# ProPrj_ESP-ARGB_2026-06-01.net
KiCad netlist of a schematic drawn in EasyEDA Pro
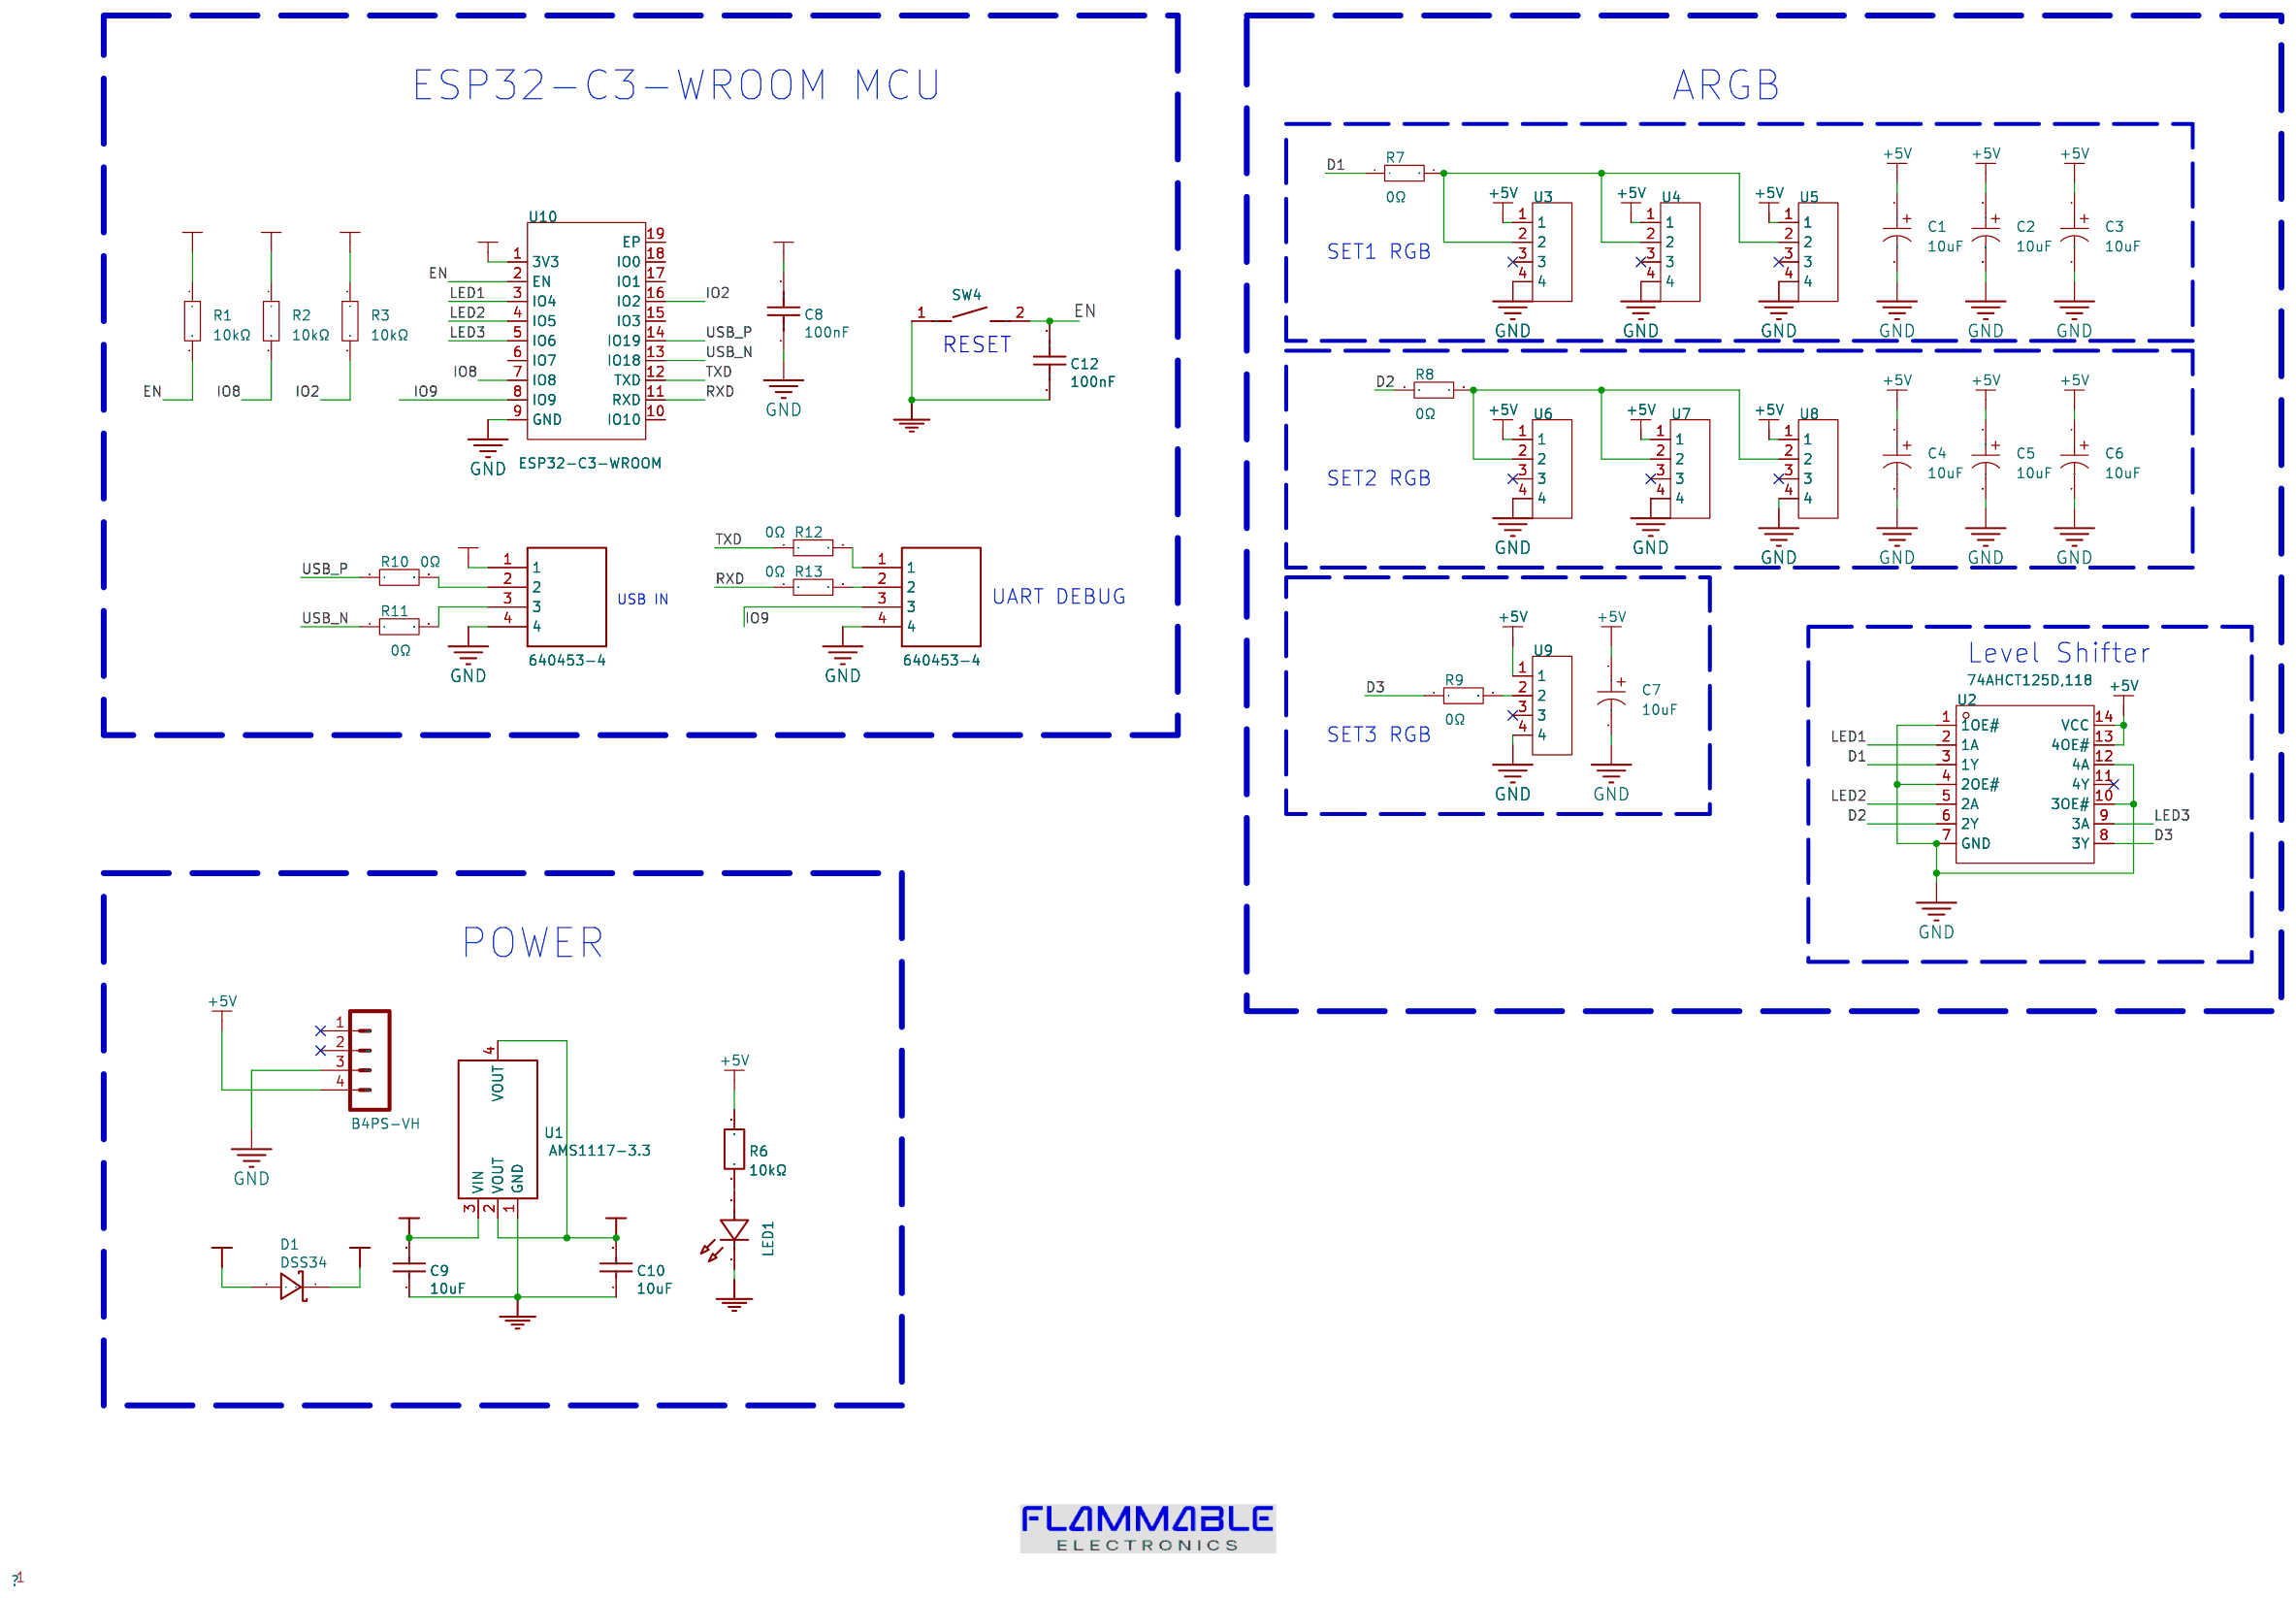
[diagram p0: schematic sheet]

(export (version "E")
  (design (tool "Eeschema 10.0.6"))
  (components
    (comp (ref "C1")
      (value "10uF")
      (footprint "easyedapro:CAP-SMD_BD4.0-L4.3-W4.3-LS5.0-FD")
      (fields
        (field (name "Manufacturer Part") "RVT1E100M0405 10UF 25V")
        (field (name "Manufacturer") "DMBJ(振宝佳)")
      )
      (libsource (lib "easyedapro") (part "RVT1E100M0405 10UF 25V"))
    )
    (comp (ref "C2")
      (value "10uF")
      (footprint "easyedapro:CAP-SMD_BD4.0-L4.3-W4.3-LS5.0-FD")
      (fields
        (field (name "Manufacturer Part") "RVT1E100M0405 10UF 25V")
        (field (name "Manufacturer") "DMBJ(振宝佳)")
      )
      (libsource (lib "easyedapro") (part "RVT1E100M0405 10UF 25V"))
    )
    (comp (ref "C3")
      (value "10uF")
      (footprint "easyedapro:CAP-SMD_BD4.0-L4.3-W4.3-LS5.0-FD")
      (fields
        (field (name "Manufacturer Part") "RVT1E100M0405 10UF 25V")
        (field (name "Manufacturer") "DMBJ(振宝佳)")
      )
      (libsource (lib "easyedapro") (part "RVT1E100M0405 10UF 25V"))
    )
    (comp (ref "C4")
      (value "10uF")
      (footprint "easyedapro:CAP-SMD_BD4.0-L4.3-W4.3-LS5.0-FD")
      (fields
        (field (name "Manufacturer Part") "RVT1E100M0405 10UF 25V")
        (field (name "Manufacturer") "DMBJ(振宝佳)")
      )
      (libsource (lib "easyedapro") (part "RVT1E100M0405 10UF 25V"))
    )
    (comp (ref "C5")
      (value "10uF")
      (footprint "easyedapro:CAP-SMD_BD4.0-L4.3-W4.3-LS5.0-FD")
      (fields
        (field (name "Manufacturer Part") "RVT1E100M0405 10UF 25V")
        (field (name "Manufacturer") "DMBJ(振宝佳)")
      )
      (libsource (lib "easyedapro") (part "RVT1E100M0405 10UF 25V"))
    )
    (comp (ref "C6")
      (value "10uF")
      (footprint "easyedapro:CAP-SMD_BD4.0-L4.3-W4.3-LS5.0-FD")
      (fields
        (field (name "Manufacturer Part") "RVT1E100M0405 10UF 25V")
        (field (name "Manufacturer") "DMBJ(振宝佳)")
      )
      (libsource (lib "easyedapro") (part "RVT1E100M0405 10UF 25V"))
    )
    (comp (ref "C7")
      (value "10uF")
      (footprint "easyedapro:CAP-SMD_BD4.0-L4.3-W4.3-LS5.0-FD")
      (fields
        (field (name "Manufacturer Part") "RVT1E100M0405 10UF 25V")
        (field (name "Manufacturer") "DMBJ(振宝佳)")
      )
      (libsource (lib "easyedapro") (part "RVT1E100M0405 10UF 25V"))
    )
    (comp (ref "C8")
      (value "100nF")
      (footprint "easyedapro:C0805")
      (fields (field (name "Manufacturer Part") "C2012X7R1H104KT0J0N") (field (name "Manufacturer") "TDK"))
      (libsource (lib "easyedapro") (part "100nF"))
    )
    (comp (ref "C9")
      (value "10uF")
      (footprint "easyedapro:C0805")
      (fields
        (field (name "Manufacturer Part") "CL21A106KOQNNNE")
        (field (name "Manufacturer") "SAMSUNG(三星)")
      )
      (libsource (lib "easyedapro") (part "10uF"))
    )
    (comp (ref "C10")
      (value "10uF")
      (footprint "easyedapro:C0805")
      (fields
        (field (name "Manufacturer Part") "CL21A106KOQNNNE")
        (field (name "Manufacturer") "SAMSUNG(三星)")
      )
      (libsource (lib "easyedapro") (part "10uF"))
    )
    (comp (ref "C12")
      (value "100nF")
      (footprint "easyedapro:C0805")
      (fields (field (name "Manufacturer Part") "C2012X7R1H104KT0J0N") (field (name "Manufacturer") "TDK"))
      (libsource (lib "easyedapro") (part "100nF"))
    )
    (comp (ref "D1")
      (value "DSS34")
      (footprint "easyedapro:SOD-123_L2.8-W1.8-LS3.7-RD")
      (fields (field (name "Manufacturer") "星海"))
      (libsource (lib "easyedapro") (part "DSS34"))
    )
    (comp (ref "LED1")
      (value "SF-RED")
      (footprint "easyedapro:LED0805-RD_RED")
      (fields (field (name "Manufacturer Part") "0805 SF-Red") (field (name "Contributor") "lcsc"))
      (libsource (lib "easyedapro") (part "SF-RED"))
    )
    (comp (ref "R1")
      (value "10kΩ")
      (footprint "easyedapro:R0805")
      (fields
        (field (name "Manufacturer Part") "0805W8F1002T5E")
        (field (name "Manufacturer") "UNI-ROYAL(厚声)")
      )
      (libsource (lib "easyedapro") (part "0805W8F1002T5E"))
    )
    (comp (ref "R2")
      (value "10kΩ")
      (footprint "easyedapro:R0805")
      (fields
        (field (name "Manufacturer Part") "0805W8F1002T5E")
        (field (name "Manufacturer") "UNI-ROYAL(厚声)")
      )
      (libsource (lib "easyedapro") (part "0805W8F1002T5E"))
    )
    (comp (ref "R3")
      (value "10kΩ")
      (footprint "easyedapro:R0805")
      (fields
        (field (name "Manufacturer Part") "0805W8F1002T5E")
        (field (name "Manufacturer") "UNI-ROYAL(厚声)")
      )
      (libsource (lib "easyedapro") (part "0805W8F1002T5E"))
    )
    (comp (ref "R6")
      (value "10kΩ")
      (footprint "easyedapro:R0805")
      (fields
        (field (name "Manufacturer Part") "TNPW080510K0BETA")
        (field (name "Manufacturer") "VISHAY(威世)")
        (field (name "Contributor") "lcsc")
      )
      (libsource (lib "easyedapro") (part "10kΩ"))
    )
    (comp (ref "R7")
      (value "0Ω")
      (footprint "easyedapro:R0805")
      (fields
        (field (name "Manufacturer Part") "0805W8F0000T5E")
        (field (name "Manufacturer") "UNI-ROYAL(厚声)")
      )
      (libsource (lib "easyedapro") (part "0805W8F0000T5E"))
    )
    (comp (ref "R8")
      (value "0Ω")
      (footprint "easyedapro:R0805")
      (fields
        (field (name "Manufacturer Part") "0805W8F0000T5E")
        (field (name "Manufacturer") "UNI-ROYAL(厚声)")
      )
      (libsource (lib "easyedapro") (part "0805W8F0000T5E"))
    )
    (comp (ref "R9")
      (value "0Ω")
      (footprint "easyedapro:R0805")
      (fields
        (field (name "Manufacturer Part") "0805W8F0000T5E")
        (field (name "Manufacturer") "UNI-ROYAL(厚声)")
      )
      (libsource (lib "easyedapro") (part "0805W8F0000T5E"))
    )
    (comp (ref "R10")
      (value "0Ω")
      (footprint "easyedapro:R0805")
      (fields
        (field (name "Manufacturer Part") "0805W8F0000T5E")
        (field (name "Manufacturer") "UNI-ROYAL(厚声)")
      )
      (libsource (lib "easyedapro") (part "0805W8F0000T5E"))
    )
    (comp (ref "R11")
      (value "0Ω")
      (footprint "easyedapro:R0805")
      (fields
        (field (name "Manufacturer Part") "0805W8F0000T5E")
        (field (name "Manufacturer") "UNI-ROYAL(厚声)")
      )
      (libsource (lib "easyedapro") (part "0805W8F0000T5E"))
    )
    (comp (ref "R12")
      (value "0Ω")
      (footprint "easyedapro:R0805")
      (fields
        (field (name "Manufacturer Part") "0805W8F0000T5E")
        (field (name "Manufacturer") "UNI-ROYAL(厚声)")
      )
      (libsource (lib "easyedapro") (part "0805W8F0000T5E"))
    )
    (comp (ref "R13")
      (value "0Ω")
      (footprint "easyedapro:R0805")
      (fields
        (field (name "Manufacturer Part") "0805W8F0000T5E")
        (field (name "Manufacturer") "UNI-ROYAL(厚声)")
      )
      (libsource (lib "easyedapro") (part "0805W8F0000T5E"))
    )
    (comp (ref "SW4")
      (value "TS-1088-AR02016")
      (footprint "easyedapro:SW-SMD_L3.9-W3.0-P4.45")
      (fields (field (name "Manufacturer") "XUNPU(讯普)") (field (name "Contributor") "LCSC"))
      (libsource (lib "easyedapro") (part "TS-1088-AR02016"))
    )
    (comp (ref "U1")
      (value "AMS1117-3.3")
      (footprint "easyedapro:SOT-223-3_L6.5-W3.4-P2.30-LS7.0-BR")
      (fields (field (name "Manufacturer") "AMS"))
      (libsource (lib "easyedapro") (part "AMS1117-3.3"))
    )
    (comp (ref "U2")
      (value "74AHCT125D,118")
      (footprint "easyedapro:SOP-14_L8.6-W3.9-P1.27-LS6.0-BL")
      (fields (field (name "Manufacturer") "Nexperia(安世)"))
      (libsource (lib "easyedapro") (part "74AHCT125D,118"))
    )
    (comp (ref "U3")
      (value "P125-1104A0BR138A1")
      (footprint "easyedapro:HDR-TH_4P-P2.54-H-M-W10.3")
      (fields (field (name "Manufacturer") "Yxcon(宇熙精密)"))
      (libsource (lib "easyedapro") (part "P125-1104A0BR138A1"))
    )
    (comp (ref "U4")
      (value "P125-1104A0BR138A1")
      (footprint "easyedapro:HDR-TH_4P-P2.54-H-M-W10.3")
      (fields (field (name "Manufacturer") "Yxcon(宇熙精密)"))
      (libsource (lib "easyedapro") (part "P125-1104A0BR138A1"))
    )
    (comp (ref "U5")
      (value "P125-1104A0BR138A1")
      (footprint "easyedapro:HDR-TH_4P-P2.54-H-M-W10.3")
      (fields (field (name "Manufacturer") "Yxcon(宇熙精密)"))
      (libsource (lib "easyedapro") (part "P125-1104A0BR138A1"))
    )
    (comp (ref "U6")
      (value "P125-1104A0BR138A1")
      (footprint "easyedapro:HDR-TH_4P-P2.54-H-M-W10.3")
      (fields (field (name "Manufacturer") "Yxcon(宇熙精密)"))
      (libsource (lib "easyedapro") (part "P125-1104A0BR138A1"))
    )
    (comp (ref "U7")
      (value "P125-1104A0BR138A1")
      (footprint "easyedapro:HDR-TH_4P-P2.54-H-M-W10.3")
      (fields (field (name "Manufacturer") "Yxcon(宇熙精密)"))
      (libsource (lib "easyedapro") (part "P125-1104A0BR138A1"))
    )
    (comp (ref "U8")
      (value "P125-1104A0BR138A1")
      (footprint "easyedapro:HDR-TH_4P-P2.54-H-M-W10.3")
      (fields (field (name "Manufacturer") "Yxcon(宇熙精密)"))
      (libsource (lib "easyedapro") (part "P125-1104A0BR138A1"))
    )
    (comp (ref "U9")
      (value "P125-1104A0BR138A1")
      (footprint "easyedapro:HDR-TH_4P-P2.54-H-M-W10.3")
      (fields (field (name "Manufacturer") "Yxcon(宇熙精密)"))
      (libsource (lib "easyedapro") (part "P125-1104A0BR138A1"))
    )
    (comp (ref "U10")
      (value "ESP32-C3-WROOM")
      (footprint "easyedapro:BULETM-SMD_ESPRESSIF_ESP32-C3-WROOM-02-N4-4MB")
      (fields
        (field (name "Manufacturer Part") "ESP32-C3-WROOM-02-N4")
        (field (name "Manufacturer") "ESPRESSIF(乐鑫)")
      )
      (libsource (lib "easyedapro") (part "ESP32-C3-WROOM-02-N4(4MB)"))
    )
    (comp (ref "U11") (value "640453-4") (libsource (lib "easyedapro") (part "640453-4")))
    (comp (ref "U12") (value "640453-4") (libsource (lib "easyedapro") (part "640453-4")))
    (comp (ref "X1")
      (value "B4PS-VH")
      (footprint "easyedapro:B4PS-VH")
      (libsource (lib "easyedapro") (part "B4PS-VH"))
    )
  )
  (nets
    (net (code "1") (name "+3.3V") (class "Default")
      (node (ref "C10") (pin "2") (pinfunction "2_2") (pintype "input"))
      (node (ref "C8") (pin "2") (pinfunction "2_2") (pintype "unspecified"))
      (node (ref "R1") (pin "1") (pinfunction "1_1") (pintype "input"))
      (node (ref "R2") (pin "1") (pinfunction "1_1") (pintype "input"))
      (node (ref "R3") (pin "1") (pinfunction "1_1") (pintype "input"))
      (node (ref "U1") (pin "2") (pinfunction "VOUT_2") (pintype "unspecified"))
      (node (ref "U1") (pin "4") (pinfunction "VOUT_4") (pintype "unspecified"))
      (node (ref "U10") (pin "1") (pinfunction "3V3_1") (pintype "unspecified"))
    )
    (net (code "2") (name "+5V") (class "Default")
      (node (ref "C1") (pin "1") (pinfunction "1_1") (pintype "input"))
      (node (ref "C2") (pin "1") (pinfunction "1_1") (pintype "input"))
      (node (ref "C3") (pin "1") (pinfunction "1_1") (pintype "input"))
      (node (ref "C4") (pin "1") (pinfunction "1_1") (pintype "input"))
      (node (ref "C5") (pin "1") (pinfunction "1_1") (pintype "input"))
      (node (ref "C6") (pin "1") (pinfunction "1_1") (pintype "input"))
      (node (ref "C7") (pin "1") (pinfunction "1_1") (pintype "input"))
      (node (ref "C9") (pin "2") (pinfunction "2_2") (pintype "input"))
      (node (ref "D1") (pin "1") (pinfunction "K_1") (pintype "unspecified"))
      (node (ref "R6") (pin "2") (pinfunction "2_2") (pintype "unspecified"))
      (node (ref "U1") (pin "3") (pinfunction "VIN_3") (pintype "unspecified"))
      (node (ref "U2") (pin "13") (pinfunction "4OE#_13") (pintype "unspecified"))
      (node (ref "U2") (pin "14") (pinfunction "VCC_14") (pintype "unspecified"))
      (node (ref "U3") (pin "1") (pinfunction "1_1") (pintype "unspecified"))
      (node (ref "U4") (pin "1") (pinfunction "1_1") (pintype "unspecified"))
      (node (ref "U5") (pin "1") (pinfunction "1_1") (pintype "unspecified"))
      (node (ref "U6") (pin "1") (pinfunction "1_1") (pintype "unspecified"))
      (node (ref "U7") (pin "1") (pinfunction "1_1") (pintype "unspecified"))
      (node (ref "U8") (pin "1") (pinfunction "1_1") (pintype "unspecified"))
      (node (ref "U9") (pin "1") (pinfunction "1_1") (pintype "unspecified"))
      (node (ref "X1") (pin "4") (pinfunction "~_4") (pintype "unspecified"))
    )
    (net (code "3") (name "/D1") (class "Default")
      (node (ref "R7") (pin "1") (pinfunction "1_1") (pintype "input"))
      (node (ref "U2") (pin "3") (pinfunction "1Y_3") (pintype "unspecified"))
    )
    (net (code "4") (name "/D2") (class "Default")
      (node (ref "R8") (pin "1") (pinfunction "1_1") (pintype "input"))
      (node (ref "U2") (pin "6") (pinfunction "2Y_6") (pintype "unspecified"))
    )
    (net (code "5") (name "/D3") (class "Default")
      (node (ref "R9") (pin "1") (pinfunction "1_1") (pintype "input"))
      (node (ref "U2") (pin "8") (pinfunction "3Y_8") (pintype "unspecified"))
    )
    (net (code "6") (name "/EN") (class "Default")
      (node (ref "C12") (pin "2") (pinfunction "2_2") (pintype "unspecified"))
      (node (ref "R1") (pin "2") (pinfunction "2_2") (pintype "input"))
      (node (ref "SW4") (pin "2") (pinfunction "2_2") (pintype "unspecified"))
      (node (ref "U10") (pin "2") (pinfunction "EN_2") (pintype "unspecified"))
    )
    (net (code "7") (name "/IO2") (class "Default")
      (node (ref "R3") (pin "2") (pinfunction "2_2") (pintype "input"))
      (node (ref "U10") (pin "16") (pinfunction "IO2_16") (pintype "unspecified"))
    )
    (net (code "8") (name "/IO8") (class "Default")
      (node (ref "R2") (pin "2") (pinfunction "2_2") (pintype "input"))
      (node (ref "U10") (pin "7") (pinfunction "IO8_7") (pintype "unspecified"))
    )
    (net (code "9") (name "/IO9") (class "Default")
      (node (ref "U10") (pin "8") (pinfunction "IO9_8") (pintype "unspecified"))
      (node (ref "U12") (pin "3") (pinfunction "3_3") (pintype "unspecified"))
    )
    (net (code "10") (name "/LED1") (class "Default")
      (node (ref "U10") (pin "3") (pinfunction "IO4_3") (pintype "unspecified"))
      (node (ref "U2") (pin "2") (pinfunction "1A_2") (pintype "unspecified"))
    )
    (net (code "11") (name "/LED2") (class "Default")
      (node (ref "U10") (pin "4") (pinfunction "IO5_4") (pintype "unspecified"))
      (node (ref "U2") (pin "5") (pinfunction "2A_5") (pintype "unspecified"))
    )
    (net (code "12") (name "/LED3") (class "Default")
      (node (ref "U10") (pin "5") (pinfunction "IO6_5") (pintype "unspecified"))
      (node (ref "U2") (pin "9") (pinfunction "3A_9") (pintype "unspecified"))
    )
    (net (code "13") (name "/RXD") (class "Default")
      (node (ref "R13") (pin "1") (pinfunction "1_1") (pintype "input"))
      (node (ref "U10") (pin "11") (pinfunction "RXD_11") (pintype "unspecified"))
    )
    (net (code "14") (name "/TXD") (class "Default")
      (node (ref "R12") (pin "1") (pinfunction "1_1") (pintype "input"))
      (node (ref "U10") (pin "12") (pinfunction "TXD_12") (pintype "unspecified"))
    )
    (net (code "15") (name "/USB_N") (class "Default")
      (node (ref "R11") (pin "1") (pinfunction "1_1") (pintype "input"))
      (node (ref "U10") (pin "13") (pinfunction "IO18_13") (pintype "unspecified"))
    )
    (net (code "16") (name "/USB_P") (class "Default")
      (node (ref "R10") (pin "1") (pinfunction "1_1") (pintype "input"))
      (node (ref "U10") (pin "14") (pinfunction "IO19_14") (pintype "unspecified"))
    )
    (net (code "17") (name "GND") (class "Default")
      (node (ref "C1") (pin "2") (pinfunction "2_2") (pintype "input"))
      (node (ref "C10") (pin "1") (pinfunction "1_1") (pintype "input"))
      (node (ref "C12") (pin "1") (pinfunction "1_1") (pintype "unspecified"))
      (node (ref "C2") (pin "2") (pinfunction "2_2") (pintype "input"))
      (node (ref "C3") (pin "2") (pinfunction "2_2") (pintype "input"))
      (node (ref "C4") (pin "2") (pinfunction "2_2") (pintype "input"))
      (node (ref "C5") (pin "2") (pinfunction "2_2") (pintype "input"))
      (node (ref "C6") (pin "2") (pinfunction "2_2") (pintype "input"))
      (node (ref "C7") (pin "2") (pinfunction "2_2") (pintype "input"))
      (node (ref "C8") (pin "1") (pinfunction "1_1") (pintype "unspecified"))
      (node (ref "C9") (pin "1") (pinfunction "1_1") (pintype "input"))
      (node (ref "LED1") (pin "1") (pinfunction "K_1") (pintype "unspecified"))
      (node (ref "SW4") (pin "1") (pinfunction "1_1") (pintype "unspecified"))
      (node (ref "U1") (pin "1") (pinfunction "GND_1") (pintype "unspecified"))
      (node (ref "U10") (pin "9") (pinfunction "GND_9") (pintype "unspecified"))
      (node (ref "U11") (pin "4") (pinfunction "4_4") (pintype "unspecified"))
      (node (ref "U12") (pin "4") (pinfunction "4_4") (pintype "unspecified"))
      (node (ref "U2") (pin "1") (pinfunction "1OE#_1") (pintype "unspecified"))
      (node (ref "U2") (pin "10") (pinfunction "3OE#_10") (pintype "unspecified"))
      (node (ref "U2") (pin "12") (pinfunction "4A_12") (pintype "unspecified"))
      (node (ref "U2") (pin "4") (pinfunction "2OE#_4") (pintype "unspecified"))
      (node (ref "U2") (pin "7") (pinfunction "GND_7") (pintype "unspecified"))
      (node (ref "U3") (pin "4") (pinfunction "4_4") (pintype "unspecified"))
      (node (ref "U4") (pin "4") (pinfunction "4_4") (pintype "unspecified"))
      (node (ref "U5") (pin "4") (pinfunction "4_4") (pintype "unspecified"))
      (node (ref "U6") (pin "4") (pinfunction "4_4") (pintype "unspecified"))
      (node (ref "U7") (pin "4") (pinfunction "4_4") (pintype "unspecified"))
      (node (ref "U8") (pin "4") (pinfunction "4_4") (pintype "unspecified"))
      (node (ref "U9") (pin "4") (pinfunction "4_4") (pintype "unspecified"))
      (node (ref "X1") (pin "3") (pinfunction "~_3") (pintype "unspecified"))
    )
    (net (code "18") (name "Net-(LED1-A)") (class "Default")
      (node (ref "LED1") (pin "2") (pinfunction "A_2") (pintype "unspecified"))
      (node (ref "R6") (pin "1") (pinfunction "1_1") (pintype "unspecified"))
    )
    (net (code "19") (name "Net-(R7-Pad2)") (class "Default")
      (node (ref "R7") (pin "2") (pinfunction "2_2") (pintype "input"))
      (node (ref "U3") (pin "2") (pinfunction "2_2") (pintype "unspecified"))
      (node (ref "U4") (pin "2") (pinfunction "2_2") (pintype "unspecified"))
      (node (ref "U5") (pin "2") (pinfunction "2_2") (pintype "unspecified"))
    )
    (net (code "20") (name "Net-(R8-Pad2)") (class "Default")
      (node (ref "R8") (pin "2") (pinfunction "2_2") (pintype "input"))
      (node (ref "U6") (pin "2") (pinfunction "2_2") (pintype "unspecified"))
      (node (ref "U7") (pin "2") (pinfunction "2_2") (pintype "unspecified"))
      (node (ref "U8") (pin "2") (pinfunction "2_2") (pintype "unspecified"))
    )
    (net (code "21") (name "Net-(R9-Pad2)") (class "Default")
      (node (ref "R9") (pin "2") (pinfunction "2_2") (pintype "input"))
      (node (ref "U9") (pin "2") (pinfunction "2_2") (pintype "unspecified"))
    )
    (net (code "22") (name "Net-(R10-Pad2)") (class "Default")
      (node (ref "R10") (pin "2") (pinfunction "2_2") (pintype "input"))
      (node (ref "U11") (pin "2") (pinfunction "2_2") (pintype "unspecified"))
    )
    (net (code "23") (name "Net-(R11-Pad2)") (class "Default")
      (node (ref "R11") (pin "2") (pinfunction "2_2") (pintype "input"))
      (node (ref "U11") (pin "3") (pinfunction "3_3") (pintype "unspecified"))
    )
    (net (code "24") (name "Net-(R12-Pad2)") (class "Default")
      (node (ref "R12") (pin "2") (pinfunction "2_2") (pintype "input"))
      (node (ref "U12") (pin "1") (pinfunction "1_1") (pintype "unspecified"))
    )
    (net (code "25") (name "Net-(R13-Pad2)") (class "Default")
      (node (ref "R13") (pin "2") (pinfunction "2_2") (pintype "input"))
      (node (ref "U12") (pin "2") (pinfunction "2_2") (pintype "unspecified"))
    )
    (net (code "26") (name "VBUS") (class "Default")
      (node (ref "D1") (pin "2") (pinfunction "A_2") (pintype "unspecified"))
      (node (ref "U11") (pin "1") (pinfunction "1_1") (pintype "unspecified"))
    )
    (net (code "27") (name "unconnected-(U2-4Y-Pad11)") (class "Default")
      (node (ref "U2") (pin "11") (pinfunction "4Y_11") (pintype "unspecified+no_connect"))
    )
    (net (code "28") (name "unconnected-(U3-Pad3)") (class "Default")
      (node (ref "U3") (pin "3") (pinfunction "3_3") (pintype "unspecified+no_connect"))
    )
    (net (code "29") (name "unconnected-(U4-Pad3)") (class "Default")
      (node (ref "U4") (pin "3") (pinfunction "3_3") (pintype "unspecified+no_connect"))
    )
    (net (code "30") (name "unconnected-(U5-Pad3)") (class "Default")
      (node (ref "U5") (pin "3") (pinfunction "3_3") (pintype "unspecified+no_connect"))
    )
    (net (code "31") (name "unconnected-(U6-Pad3)") (class "Default")
      (node (ref "U6") (pin "3") (pinfunction "3_3") (pintype "unspecified+no_connect"))
    )
    (net (code "32") (name "unconnected-(U7-Pad3)") (class "Default")
      (node (ref "U7") (pin "3") (pinfunction "3_3") (pintype "unspecified+no_connect"))
    )
    (net (code "33") (name "unconnected-(U8-Pad3)") (class "Default")
      (node (ref "U8") (pin "3") (pinfunction "3_3") (pintype "unspecified+no_connect"))
    )
    (net (code "34") (name "unconnected-(U9-Pad3)") (class "Default")
      (node (ref "U9") (pin "3") (pinfunction "3_3") (pintype "unspecified+no_connect"))
    )
    (net (code "35") (name "unconnected-(U10-EP-Pad19)") (class "Default")
      (node (ref "U10") (pin "19") (pinfunction "EP_19") (pintype "unspecified"))
    )
    (net (code "36") (name "unconnected-(U10-IO0-Pad18)") (class "Default")
      (node (ref "U10") (pin "18") (pinfunction "IO0_18") (pintype "unspecified"))
    )
    (net (code "37") (name "unconnected-(U10-IO1-Pad17)") (class "Default")
      (node (ref "U10") (pin "17") (pinfunction "IO1_17") (pintype "unspecified"))
    )
    (net (code "38") (name "unconnected-(U10-IO3-Pad15)") (class "Default")
      (node (ref "U10") (pin "15") (pinfunction "IO3_15") (pintype "unspecified"))
    )
    (net (code "39") (name "unconnected-(U10-IO7-Pad6)") (class "Default")
      (node (ref "U10") (pin "6") (pinfunction "IO7_6") (pintype "unspecified"))
    )
    (net (code "40") (name "unconnected-(U10-IO10-Pad10)") (class "Default")
      (node (ref "U10") (pin "10") (pinfunction "IO10_10") (pintype "unspecified"))
    )
    (net (code "41") (name "unconnected-(X1-~-Pad1)") (class "Default")
      (node (ref "X1") (pin "1") (pinfunction "~_1") (pintype "unspecified+no_connect"))
    )
    (net (code "42") (name "unconnected-(X1-~-Pad2)") (class "Default")
      (node (ref "X1") (pin "2") (pinfunction "~_2") (pintype "unspecified+no_connect"))
    )
  )
)
